# FanBot.net
KiCad netlist of a schematic drawn in Altium Designer
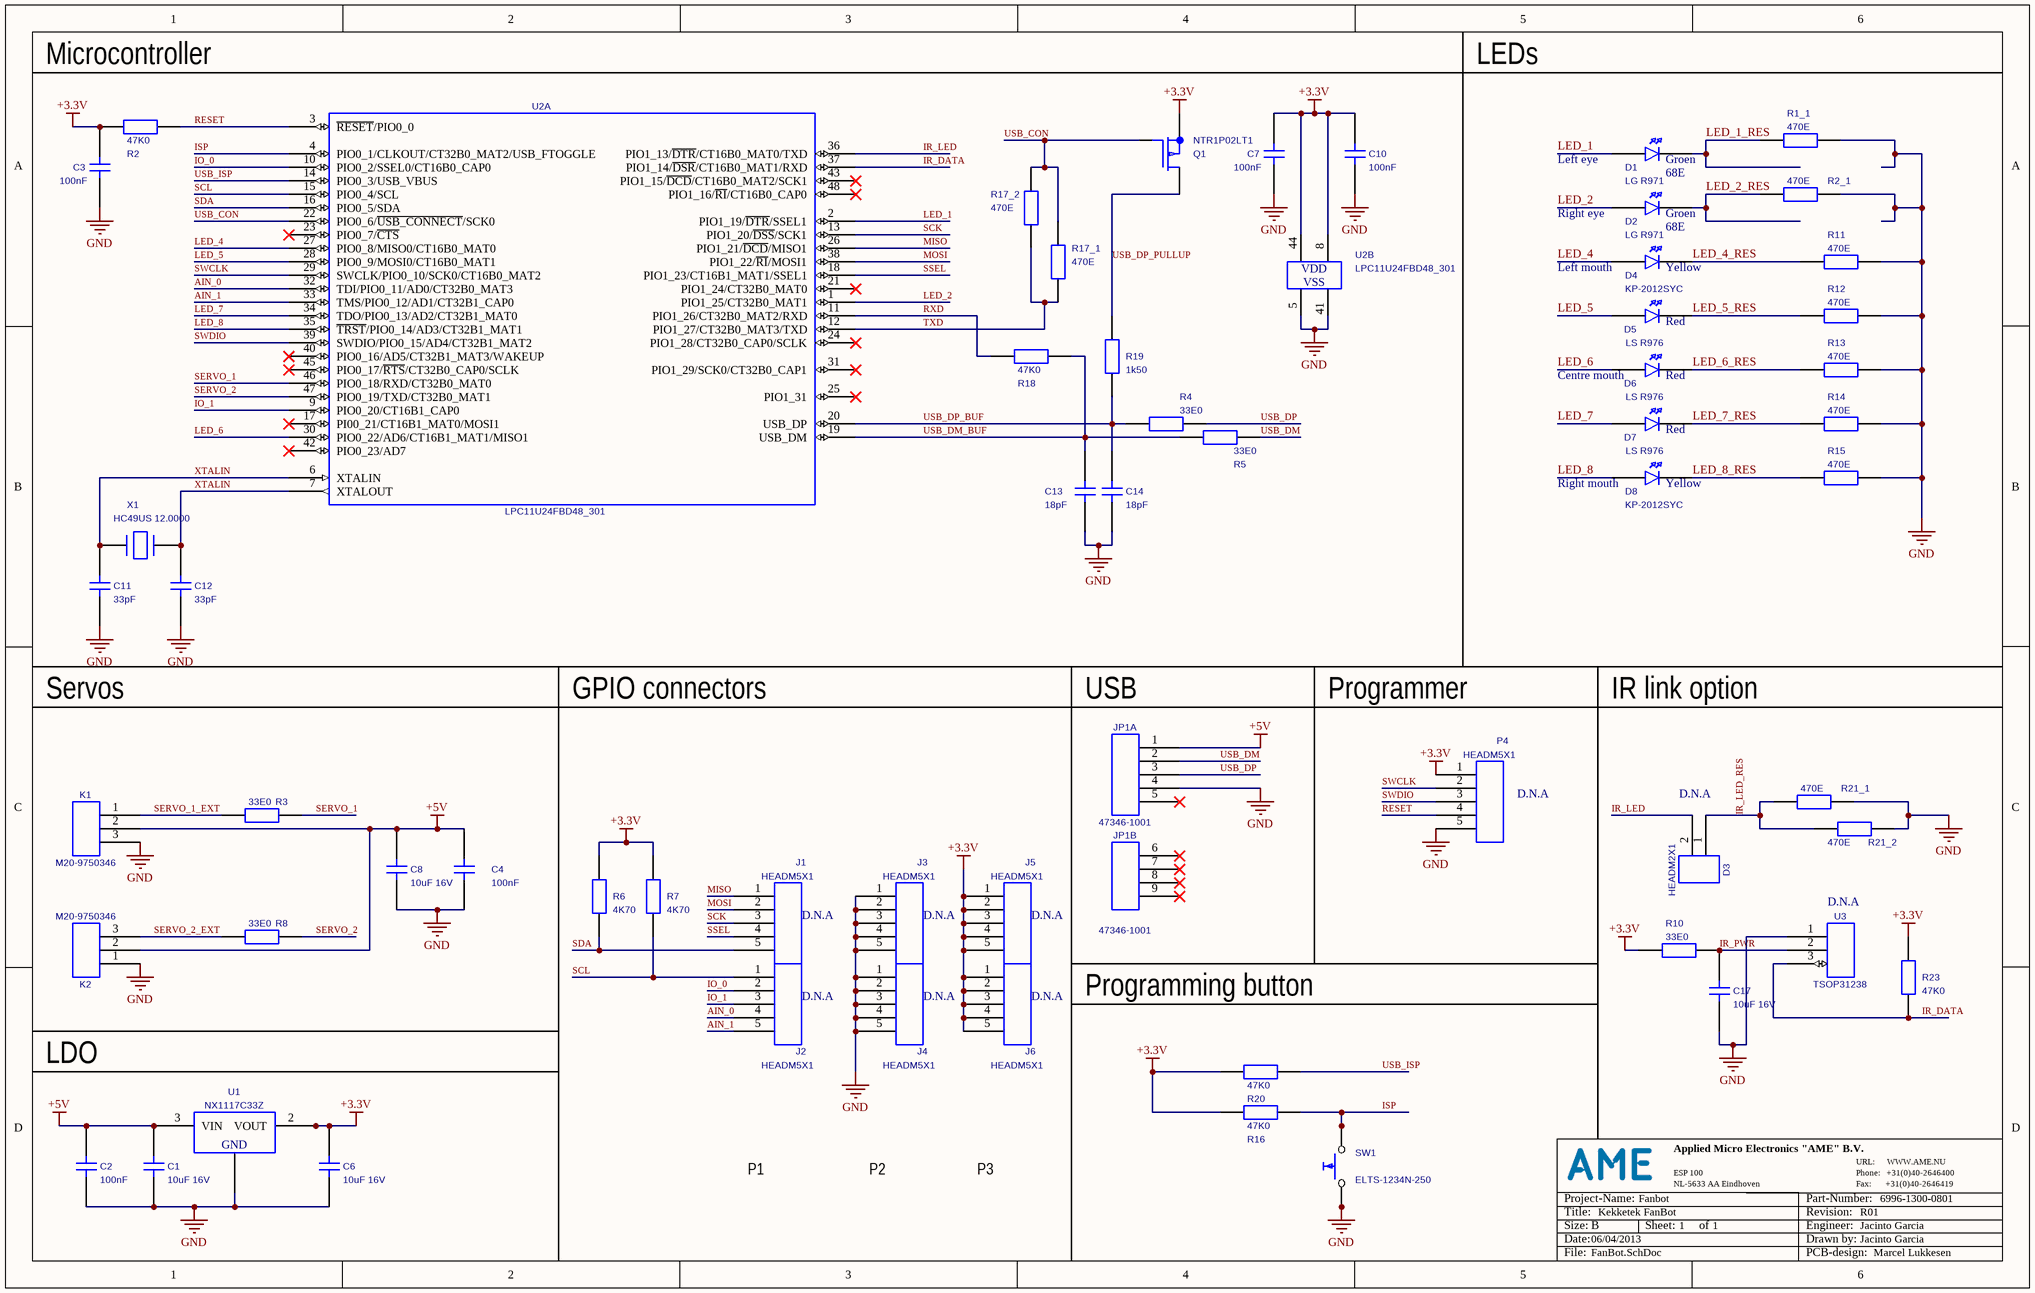
[diagram p0: FanBot.SchDoc]

(export (version "E")
  (design (tool "Eeschema 10.0.6"))
  (components
    (comp (ref "C1")
      (value "10U 0805 X5R16V")
      (footprint "C0805")
      (fields
        (field (name "PART NUMBER") "120400051105")
        (field (name "MANUFACTURER") "AVX")
        (field (name "PVALUE") "10uF 16V")
      )
      (libsource (lib "CC0805") (part "10U 0805 X5R16V"))
    )
    (comp (ref "C2")
      (value "100N 0805 X7R50V")
      (footprint "C0805")
      (fields
        (field (name "PVALUE") "100nF")
        (field (name "PART NUMBER") "120400011003")
        (field (name "MANUFACTURER") "Kemet")
      )
      (libsource (lib "CC0805") (part "100N 0805 X7R50V"))
    )
    (comp (ref "C3")
      (value "100N 0805 X7R50V")
      (footprint "C0805")
      (fields
        (field (name "PVALUE") "100nF")
        (field (name "PART NUMBER") "120400011003")
        (field (name "MANUFACTURER") "Kemet")
      )
      (libsource (lib "CC0805") (part "100N 0805 X7R50V"))
    )
    (comp (ref "C4")
      (value "100N 0805 X7R50V")
      (footprint "C0805")
      (fields
        (field (name "PVALUE") "100nF")
        (field (name "PART NUMBER") "120400011003")
        (field (name "MANUFACTURER") "Kemet")
      )
      (libsource (lib "CC0805") (part "100N 0805 X7R50V"))
    )
    (comp (ref "C6")
      (value "10U 0805 X5R16V")
      (footprint "C0805")
      (fields
        (field (name "PART NUMBER") "120400051105")
        (field (name "MANUFACTURER") "AVX")
        (field (name "PVALUE") "10uF 16V")
      )
      (libsource (lib "CC0805") (part "10U 0805 X5R16V"))
    )
    (comp (ref "C7")
      (value "100N 0805 X7R50V")
      (footprint "C0805")
      (fields
        (field (name "PVALUE") "100nF")
        (field (name "PART NUMBER") "120400011003")
        (field (name "MANUFACTURER") "Kemet")
      )
      (libsource (lib "CC0805") (part "100N 0805 X7R50V"))
    )
    (comp (ref "C8")
      (value "10U 0805 X5R16V")
      (footprint "C0805")
      (fields
        (field (name "PART NUMBER") "120400051105")
        (field (name "MANUFACTURER") "AVX")
        (field (name "PVALUE") "10uF 16V")
      )
      (libsource (lib "CC0805") (part "10U 0805 X5R16V"))
    )
    (comp (ref "C10")
      (value "100N 0805 X7R50V")
      (footprint "C0805")
      (fields
        (field (name "PVALUE") "100nF")
        (field (name "PART NUMBER") "120400011003")
        (field (name "MANUFACTURER") "Kemet")
      )
      (libsource (lib "CC0805") (part "100N 0805 X7R50V"))
    )
    (comp (ref "C11")
      (value "33P 0805 X7R50V")
      (footprint "C0805")
      (fields
        (field (name "PVALUE") "33pF")
        (field (name "PART NUMBER") "120400013309")
        (field (name "MANUFACTURER") "Kemet")
      )
      (libsource (lib "CC0805") (part "33P 0805 X7R50V"))
    )
    (comp (ref "C12")
      (value "33P 0805 X7R50V")
      (footprint "C0805")
      (fields
        (field (name "PVALUE") "33pF")
        (field (name "PART NUMBER") "120400013309")
        (field (name "MANUFACTURER") "Kemet")
      )
      (libsource (lib "CC0805") (part "33P 0805 X7R50V"))
    )
    (comp (ref "C13")
      (value "18P 0805 X7R50V")
      (footprint "C0805")
      (fields
        (field (name "PVALUE") "18pF")
        (field (name "PART NUMBER") "120400011809")
        (field (name "MANUFACTURER") "Kemet")
      )
      (libsource (lib "CC0805") (part "18P 0805 X7R50V"))
    )
    (comp (ref "C14")
      (value "18P 0805 X7R50V")
      (footprint "C0805")
      (fields
        (field (name "PVALUE") "18pF")
        (field (name "PART NUMBER") "120400011809")
        (field (name "MANUFACTURER") "Kemet")
      )
      (libsource (lib "CC0805") (part "18P 0805 X7R50V"))
    )
    (comp (ref "C17")
      (value "10U 0805 X5R16V")
      (footprint "C0805")
      (fields
        (field (name "PART NUMBER") "120400051105")
        (field (name "MANUFACTURER") "AVX")
        (field (name "PVALUE") "10uF 16V")
      )
      (libsource (lib "CC0805") (part "10U 0805 X5R16V"))
    )
    (comp (ref "D1")
      (value "LG R971")
      (footprint "0805 LED OSR")
      (fields (field (name "PART NUMBER") "206000010001") (field (name "MANUFACTURER") "Osram"))
      (libsource (lib "DIS_AM") (part "LG R971"))
    )
    (comp (ref "D2")
      (value "LG R971")
      (footprint "0805 LED OSR")
      (fields (field (name "PART NUMBER") "206000010001") (field (name "MANUFACTURER") "Osram"))
      (libsource (lib "DIS_AM") (part "LG R971"))
    )
    (comp (ref "D3")
      (value "HEADM2X1")
      (footprint "HEADM2X1")
      (fields (field (name "PART NUMBER") "505000030003") (field (name "MANUFACTURER") "Harwin"))
      (libsource (lib "CONN_AM") (part "HEADM2X1"))
    )
    (comp (ref "D4")
      (value "KP-2012SYC")
      (footprint "0805 LED")
      (fields (field (name "PART NUMBER") "206000010035") (field (name "MANUFACTURER") "Kingbright"))
      (libsource (lib "DIS_AM") (part "KP-2012SYC"))
    )
    (comp (ref "D5")
      (value "LS R976")
      (footprint "0805 LED OSR")
      (fields (field (name "PART NUMBER") "206000010024") (field (name "MANUFACTURER") "Osram"))
      (libsource (lib "DIS_AM") (part "LS R976"))
    )
    (comp (ref "D6")
      (value "LS R976")
      (footprint "0805 LED OSR")
      (fields (field (name "PART NUMBER") "206000010024") (field (name "MANUFACTURER") "Osram"))
      (libsource (lib "DIS_AM") (part "LS R976"))
    )
    (comp (ref "D7")
      (value "LS R976")
      (footprint "0805 LED OSR")
      (fields (field (name "PART NUMBER") "206000010024") (field (name "MANUFACTURER") "Osram"))
      (libsource (lib "DIS_AM") (part "LS R976"))
    )
    (comp (ref "D8")
      (value "KP-2012SYC")
      (footprint "0805 LED")
      (fields (field (name "PART NUMBER") "206000010035") (field (name "MANUFACTURER") "Kingbright"))
      (libsource (lib "DIS_AM") (part "KP-2012SYC"))
    )
    (comp (ref "J1")
      (value "HEADM5X1")
      (footprint "M20-9770522")
      (fields (field (name "PART NUMBER") "505000080023") (field (name "MANUFACTURER") "Harwin"))
      (libsource (lib "CONN_AM") (part "HEADM5X1"))
    )
    (comp (ref "J2")
      (value "HEADM5X1")
      (footprint "M20-9770522")
      (fields (field (name "PART NUMBER") "505000080023") (field (name "MANUFACTURER") "Harwin"))
      (libsource (lib "CONN_AM") (part "HEADM5X1"))
    )
    (comp (ref "J3")
      (value "HEADM5X1")
      (footprint "M20-9770522")
      (fields (field (name "PART NUMBER") "505000080023") (field (name "MANUFACTURER") "Harwin"))
      (libsource (lib "CONN_AM") (part "HEADM5X1"))
    )
    (comp (ref "J4")
      (value "HEADM5X1")
      (footprint "M20-9770522")
      (fields (field (name "PART NUMBER") "505000080023") (field (name "MANUFACTURER") "Harwin"))
      (libsource (lib "CONN_AM") (part "HEADM5X1"))
    )
    (comp (ref "J5")
      (value "HEADM5X1")
      (footprint "M20-9770522")
      (fields (field (name "PART NUMBER") "505000080023") (field (name "MANUFACTURER") "Harwin"))
      (libsource (lib "CONN_AM") (part "HEADM5X1"))
    )
    (comp (ref "J6")
      (value "HEADM5X1")
      (footprint "M20-9770522")
      (fields (field (name "PART NUMBER") "505000080023") (field (name "MANUFACTURER") "Harwin"))
      (libsource (lib "CONN_AM") (part "HEADM5X1"))
    )
    (comp (ref "JP1")
      (value "47346-1001")
      (footprint "47346-0001")
      (fields (field (name "PART NUMBER") "509000220067") (field (name "MANUFACTURER") "Molex"))
      (libsource (lib "CONN_AM") (part "47346-1001"))
    )
    (comp (ref "K1")
      (value "M20-9750346")
      (footprint "M20-9750346")
      (fields (field (name "PART NUMBER") "505000080120") (field (name "MANUFACTURER") "Harwin"))
      (libsource (lib "CONN_AM") (part "M20-9750346"))
    )
    (comp (ref "K2")
      (value "M20-9750346")
      (footprint "M20-9750346")
      (fields (field (name "PART NUMBER") "505000080120") (field (name "MANUFACTURER") "Harwin"))
      (libsource (lib "CONN_AM") (part "M20-9750346"))
    )
    (comp (ref "P4")
      (value "HEADM5X1")
      (footprint "M20-9770522")
      (fields (field (name "PART NUMBER") "505000080023") (field (name "MANUFACTURER") "Harwin"))
      (libsource (lib "CONN_AM") (part "HEADM5X1"))
    )
    (comp (ref "Q1")
      (value "NTR1P02LT1")
      (footprint "SOT-23")
      (fields (field (name "PART NUMBER") "222000010018") (field (name "MANUFACTURER") "ON Semiconductor"))
      (libsource (lib "DIS_AM") (part "NTR1P02LT1"))
    )
    (comp (ref "R1_1")
      (value "470E 0805 1%")
      (footprint "R0805")
      (fields
        (field (name "PVALUE") "470E")
        (field (name "PART NUMBER") "110200014700")
        (field (name "MANUFACTURER") "ASJ")
      )
      (libsource (lib "RM08051") (part "470E 0805 1%"))
    )
    (comp (ref "R2")
      (value "47K0 0805 1%")
      (footprint "R0805")
      (fields
        (field (name "PVALUE") "47K0")
        (field (name "PART NUMBER") "110200014702")
        (field (name "MANUFACTURER") "ASJ")
      )
      (libsource (lib "RM08051") (part "47K0 0805 1%"))
    )
    (comp (ref "R2_1")
      (value "470E 0805 1%")
      (footprint "R0805")
      (fields
        (field (name "PVALUE") "470E")
        (field (name "PART NUMBER") "110200014700")
        (field (name "MANUFACTURER") "ASJ")
      )
      (libsource (lib "RM08051") (part "470E 0805 1%"))
    )
    (comp (ref "R3")
      (value "33E0 0805 1%")
      (footprint "R0805")
      (fields
        (field (name "PART NUMBER") "110200013309")
        (field (name "MANUFACTURER") "Yageo")
        (field (name "PVALUE") "33E0")
      )
      (libsource (lib "RM08051") (part "33E0 0805 1%"))
    )
    (comp (ref "R4")
      (value "33E0 0805 1%")
      (footprint "R0805")
      (fields
        (field (name "PART NUMBER") "110200013309")
        (field (name "MANUFACTURER") "Yageo")
        (field (name "PVALUE") "33E0")
      )
      (libsource (lib "RM08051") (part "33E0 0805 1%"))
    )
    (comp (ref "R5")
      (value "33E0 0805 1%")
      (footprint "R0805")
      (fields
        (field (name "PART NUMBER") "110200013309")
        (field (name "MANUFACTURER") "Yageo")
        (field (name "PVALUE") "33E0")
      )
      (libsource (lib "RM08051") (part "33E0 0805 1%"))
    )
    (comp (ref "R6")
      (value "4K70 0805 1%")
      (footprint "R0805")
      (fields
        (field (name "PVALUE") "4K70")
        (field (name "PART NUMBER") "110200014701")
        (field (name "MANUFACTURER") "ASJ")
      )
      (libsource (lib "RM08051") (part "4K70 0805 1%"))
    )
    (comp (ref "R7")
      (value "4K70 0805 1%")
      (footprint "R0805")
      (fields
        (field (name "PVALUE") "4K70")
        (field (name "PART NUMBER") "110200014701")
        (field (name "MANUFACTURER") "ASJ")
      )
      (libsource (lib "RM08051") (part "4K70 0805 1%"))
    )
    (comp (ref "R8")
      (value "33E0 0805 1%")
      (footprint "R0805")
      (fields
        (field (name "PART NUMBER") "110200013309")
        (field (name "MANUFACTURER") "Yageo")
        (field (name "PVALUE") "33E0")
      )
      (libsource (lib "RM08051") (part "33E0 0805 1%"))
    )
    (comp (ref "R10")
      (value "33E0 0805 1%")
      (footprint "R0805")
      (fields
        (field (name "PVALUE") "33E0")
        (field (name "PART NUMBER") "110200013309")
        (field (name "MANUFACTURER") "Yageo")
      )
      (libsource (lib "RM08051") (part "33E0 0805 1%"))
    )
    (comp (ref "R11")
      (value "470E 0805 1%")
      (footprint "R0805")
      (fields
        (field (name "PVALUE") "470E")
        (field (name "PART NUMBER") "110200014700")
        (field (name "MANUFACTURER") "ASJ")
      )
      (libsource (lib "RM08051") (part "470E 0805 1%"))
    )
    (comp (ref "R12")
      (value "470E 0805 1%")
      (footprint "R0805")
      (fields
        (field (name "PVALUE") "470E")
        (field (name "PART NUMBER") "110200014700")
        (field (name "MANUFACTURER") "ASJ")
      )
      (libsource (lib "RM08051") (part "470E 0805 1%"))
    )
    (comp (ref "R13")
      (value "470E 0805 1%")
      (footprint "R0805")
      (fields
        (field (name "PVALUE") "470E")
        (field (name "PART NUMBER") "110200014700")
        (field (name "MANUFACTURER") "ASJ")
      )
      (libsource (lib "RM08051") (part "470E 0805 1%"))
    )
    (comp (ref "R14")
      (value "470E 0805 1%")
      (footprint "R0805")
      (fields
        (field (name "PVALUE") "470E")
        (field (name "PART NUMBER") "110200014700")
        (field (name "MANUFACTURER") "ASJ")
      )
      (libsource (lib "RM08051") (part "470E 0805 1%"))
    )
    (comp (ref "R15")
      (value "470E 0805 1%")
      (footprint "R0805")
      (fields
        (field (name "PVALUE") "470E")
        (field (name "PART NUMBER") "110200014700")
        (field (name "MANUFACTURER") "ASJ")
      )
      (libsource (lib "RM08051") (part "470E 0805 1%"))
    )
    (comp (ref "R16")
      (value "47K0 0805 1%")
      (footprint "R0805")
      (fields
        (field (name "PVALUE") "47K0")
        (field (name "PART NUMBER") "110200014702")
        (field (name "MANUFACTURER") "ASJ")
      )
      (libsource (lib "RM08051") (part "47K0 0805 1%"))
    )
    (comp (ref "R17_1")
      (value "470E 0805 1%")
      (footprint "R0805")
      (fields
        (field (name "PVALUE") "470E")
        (field (name "PART NUMBER") "110200014700")
        (field (name "MANUFACTURER") "ASJ")
      )
      (libsource (lib "RM08051") (part "470E 0805 1%"))
    )
    (comp (ref "R17_2")
      (value "470E 0805 1%")
      (footprint "R0805")
      (fields
        (field (name "PVALUE") "470E")
        (field (name "PART NUMBER") "110200014700")
        (field (name "MANUFACTURER") "ASJ")
      )
      (libsource (lib "RM08051") (part "470E 0805 1%"))
    )
    (comp (ref "R18")
      (value "47K0 0805 1%")
      (footprint "R0805")
      (fields
        (field (name "PVALUE") "47K0")
        (field (name "PART NUMBER") "110200014702")
        (field (name "MANUFACTURER") "ASJ")
      )
      (libsource (lib "RM08051") (part "47K0 0805 1%"))
    )
    (comp (ref "R19")
      (value "1K50 0805 1%")
      (footprint "R0805")
      (fields
        (field (name "PVALUE") "1k50")
        (field (name "PART NUMBER") "110200011501")
        (field (name "MANUFACTURER") "ASJ")
      )
      (libsource (lib "RM08051") (part "1K50 0805 1%"))
    )
    (comp (ref "R20")
      (value "47K0 0805 1%")
      (footprint "R0805")
      (fields
        (field (name "PVALUE") "47K0")
        (field (name "PART NUMBER") "110200014702")
        (field (name "MANUFACTURER") "ASJ")
      )
      (libsource (lib "RM08051") (part "47K0 0805 1%"))
    )
    (comp (ref "R21_1")
      (value "470E 0805 1%")
      (footprint "R0805")
      (fields
        (field (name "PVALUE") "470E")
        (field (name "PART NUMBER") "110200014700")
        (field (name "MANUFACTURER") "ASJ")
      )
      (libsource (lib "RM08051") (part "470E 0805 1%"))
    )
    (comp (ref "R21_2")
      (value "470E 0805 1%")
      (footprint "R0805")
      (fields
        (field (name "PVALUE") "470E")
        (field (name "PART NUMBER") "110200014700")
        (field (name "MANUFACTURER") "ASJ")
      )
      (libsource (lib "RM08051") (part "470E 0805 1%"))
    )
    (comp (ref "R23")
      (value "47K0 0805 1%")
      (footprint "R0805")
      (fields
        (field (name "PVALUE") "47K0")
        (field (name "PART NUMBER") "110200014702")
        (field (name "MANUFACTURER") "ASJ")
      )
      (libsource (lib "RM08051") (part "47K0 0805 1%"))
    )
    (comp (ref "SW1")
      (value "ELTS-1234N-250")
      (footprint "ELTS-1234N")
      (fields (field (name "PART NUMBER") "513000010022") (field (name "MANUFACTURER") "Eledis"))
      (libsource (lib "ELEC_AM") (part "ELTS-1234N-250"))
    )
    (comp (ref "U1")
      (value "NX1117C33Z")
      (footprint "SOT-223")
      (fields (field (name "PART NUMBER") "330000010048") (field (name "MANUFACTURER") "NXP Semiconductor"))
      (libsource (lib "REGULATORS") (part "NX1117C33Z"))
    )
    (comp (ref "U2")
      (value "LPC11U24FBD48_301")
      (footprint "LQFP48")
      (fields (field (name "PART NUMBER") "411000010007") (field (name "MANUFACTURER") "NXP Semiconductor"))
      (libsource (lib "MICRO") (part "LPC11U24FBD48_301"))
    )
    (comp (ref "U3")
      (value "TSOP31238")
      (footprint "TSOP312")
      (fields (field (name "PART NUMBER") "324000010007") (field (name "MANUFACTURER") "Vishay"))
      (libsource (lib "DIS_AM") (part "TSOP31238"))
    )
    (comp (ref "X1")
      (value "HC49US 12.0000")
      (footprint "HC49/4HSMX")
      (fields (field (name "PART NUMBER") "140000010015") (field (name "MANUFACTURER") "Hong Kong Crystals"))
      (libsource (lib "XTAL") (part "HC49US 12.0000"))
    )
  )
  (nets
    (net (code "1") (name "+3.3V") (class "Default")
      (node (ref "C10") (pin "1") (pinfunction "1_1") (pintype "passive"))
      (node (ref "C3") (pin "1") (pinfunction "1_1") (pintype "passive"))
      (node (ref "C6") (pin "1") (pinfunction "1_1") (pintype "passive"))
      (node (ref "C7") (pin "1") (pinfunction "1_1") (pintype "passive"))
      (node (ref "J5") (pin "1") (pinfunction "A1_1") (pintype "passive"))
      (node (ref "J5") (pin "2") (pinfunction "A2_2") (pintype "passive"))
      (node (ref "J5") (pin "3") (pinfunction "A3_3") (pintype "passive"))
      (node (ref "J5") (pin "4") (pinfunction "A4_4") (pintype "passive"))
      (node (ref "J5") (pin "5") (pinfunction "A5_5") (pintype "passive"))
      (node (ref "J6") (pin "1") (pinfunction "A1_1") (pintype "passive"))
      (node (ref "J6") (pin "2") (pinfunction "A2_2") (pintype "passive"))
      (node (ref "J6") (pin "3") (pinfunction "A3_3") (pintype "passive"))
      (node (ref "J6") (pin "4") (pinfunction "A4_4") (pintype "passive"))
      (node (ref "J6") (pin "5") (pinfunction "A5_5") (pintype "passive"))
      (node (ref "P4") (pin "1") (pinfunction "A1_1") (pintype "passive"))
      (node (ref "Q1") (pin "2") (pinfunction "S_2") (pintype "passive"))
      (node (ref "R10") (pin "1") (pinfunction "1_1") (pintype "passive"))
      (node (ref "R16") (pin "2") (pinfunction "2_2") (pintype "passive"))
      (node (ref "R2") (pin "2") (pinfunction "2_2") (pintype "passive"))
      (node (ref "R20") (pin "2") (pinfunction "2_2") (pintype "passive"))
      (node (ref "R23") (pin "1") (pinfunction "1_1") (pintype "passive"))
      (node (ref "R6") (pin "1") (pinfunction "1_1") (pintype "passive"))
      (node (ref "R7") (pin "1") (pinfunction "1_1") (pintype "passive"))
      (node (ref "U1") (pin "2") (pinfunction "VOUT_2") (pintype "power_in"))
      (node (ref "U1") (pin "4") (pinfunction "VOUT_4") (pintype "power_in"))
      (node (ref "U2") (pin "44") (pinfunction "VDD_44") (pintype "power_in"))
      (node (ref "U2") (pin "8") (pinfunction "VDD_8") (pintype "power_in"))
    )
    (net (code "2") (name "+5V") (class "Default")
      (node (ref "C1") (pin "1") (pinfunction "1_1") (pintype "passive"))
      (node (ref "C2") (pin "1") (pinfunction "1_1") (pintype "passive"))
      (node (ref "C4") (pin "1") (pinfunction "1_1") (pintype "passive"))
      (node (ref "C8") (pin "1") (pinfunction "1_1") (pintype "passive"))
      (node (ref "JP1") (pin "1") (pinfunction "VBUS_1") (pintype "passive"))
      (node (ref "K1") (pin "2") (pinfunction "2_2") (pintype "passive"))
      (node (ref "K2") (pin "2") (pinfunction "2_2") (pintype "passive"))
      (node (ref "U1") (pin "3") (pinfunction "VIN_3") (pintype "power_in"))
    )
    (net (code "3") (name "/AIN_0") (class "Default")
      (node (ref "J2") (pin "4") (pinfunction "A4_4") (pintype "passive"))
      (node (ref "U2") (pin "32") (pinfunction "TDI/PIO0_11/AD0/CT32B0_MAT3_32") (pintype "bidirectional"))
    )
    (net (code "4") (name "/AIN_1") (class "Default")
      (node (ref "J2") (pin "5") (pinfunction "A5_5") (pintype "passive"))
      (node (ref "U2") (pin "33") (pinfunction "TMS/PIO0_12/AD1/CT32B1_CAP0_33") (pintype "bidirectional"))
    )
    (net (code "5") (name "/IO_0") (class "Default")
      (node (ref "J2") (pin "2") (pinfunction "A2_2") (pintype "passive"))
      (node (ref "U2") (pin "10") (pinfunction "PIO0_2/SSEL0/CT16B0_CAP0_10") (pintype "bidirectional"))
    )
    (net (code "6") (name "/IO_1") (class "Default")
      (node (ref "J2") (pin "3") (pinfunction "A3_3") (pintype "passive"))
      (node (ref "U2") (pin "9") (pinfunction "PIO0_20/CT16B1_CAP0_9") (pintype "bidirectional"))
    )
    (net (code "7") (name "/IR_DATA") (class "Default")
      (node (ref "R23") (pin "2") (pinfunction "2_2") (pintype "passive"))
      (node (ref "U2") (pin "37") (pinfunction "PIO1_14/~{DSR}/CT16B0_MAT1/RXD_37") (pintype "bidirectional"))
      (node (ref "U3") (pin "3") (pinfunction "OUT_3") (pintype "bidirectional"))
    )
    (net (code "8") (name "/IR_LED") (class "Default")
      (node (ref "D3") (pin "2") (pintype "passive"))
      (node (ref "U2") (pin "36") (pinfunction "PIO1_13/~{DTR}/CT16B0_MAT0/TXD_36") (pintype "bidirectional"))
    )
    (net (code "9") (name "/IR_LED_RES") (class "Default")
      (node (ref "D3") (pin "1") (pintype "passive"))
      (node (ref "R21_1") (pin "1") (pinfunction "1_1") (pintype "passive"))
      (node (ref "R21_2") (pin "1") (pinfunction "1_1") (pintype "passive"))
    )
    (net (code "10") (name "/IR_PWR") (class "Default")
      (node (ref "C17") (pin "1") (pinfunction "1_1") (pintype "passive"))
      (node (ref "R10") (pin "2") (pinfunction "2_2") (pintype "passive"))
      (node (ref "U3") (pin "2") (pinfunction "VS_2") (pintype "power_in"))
    )
    (net (code "11") (name "/ISP") (class "Default")
      (node (ref "R16") (pin "1") (pinfunction "1_1") (pintype "passive"))
      (node (ref "SW1") (pin "1") (pintype "passive"))
      (node (ref "SW1") (pin "3") (pintype "passive"))
      (node (ref "U2") (pin "4") (pinfunction "PIO0_1/CLKOUT/CT32B0_MAT2/USB_FTOGGLE_4") (pintype "bidirectional"))
    )
    (net (code "12") (name "/LED_1") (class "Default")
      (node (ref "D1") (pin "2") (pinfunction "A_2") (pintype "passive"))
      (node (ref "U2") (pin "2") (pinfunction "PIO1_19/~{DTR}/SSEL1_2") (pintype "bidirectional"))
    )
    (net (code "13") (name "/LED_1_RES") (class "Default")
      (node (ref "D1") (pin "1") (pinfunction "K_1") (pintype "passive"))
      (node (ref "R1_1") (pin "1") (pinfunction "1_1") (pintype "passive"))
    )
    (net (code "14") (name "/LED_2") (class "Default")
      (node (ref "D2") (pin "2") (pinfunction "A_2") (pintype "passive"))
      (node (ref "U2") (pin "1") (pinfunction "PIO1_25/CT32B0_MAT1_1") (pintype "bidirectional"))
    )
    (net (code "15") (name "/LED_2_RES") (class "Default")
      (node (ref "D2") (pin "1") (pinfunction "K_1") (pintype "passive"))
      (node (ref "R2_1") (pin "1") (pinfunction "1_1") (pintype "passive"))
    )
    (net (code "16") (name "/LED_4") (class "Default")
      (node (ref "D4") (pin "2") (pinfunction "A_2") (pintype "passive"))
      (node (ref "U2") (pin "27") (pinfunction "PIO0_8/MISO0/CT16B0_MAT0_27") (pintype "bidirectional"))
    )
    (net (code "17") (name "/LED_4_RES") (class "Default")
      (node (ref "D4") (pin "1") (pinfunction "K_1") (pintype "passive"))
      (node (ref "R11") (pin "1") (pinfunction "1_1") (pintype "passive"))
    )
    (net (code "18") (name "/LED_5") (class "Default")
      (node (ref "D5") (pin "2") (pinfunction "A_2") (pintype "passive"))
      (node (ref "U2") (pin "28") (pinfunction "PIO0_9/MOSI0/CT16B0_MAT1_28") (pintype "bidirectional"))
    )
    (net (code "19") (name "/LED_5_RES") (class "Default")
      (node (ref "D5") (pin "1") (pinfunction "K_1") (pintype "passive"))
      (node (ref "R12") (pin "1") (pinfunction "1_1") (pintype "passive"))
    )
    (net (code "20") (name "/LED_6") (class "Default")
      (node (ref "D6") (pin "2") (pinfunction "A_2") (pintype "passive"))
      (node (ref "U2") (pin "30") (pinfunction "PIO0_22/AD6/CT16B1_MAT1/MISO1_30") (pintype "bidirectional"))
    )
    (net (code "21") (name "/LED_6_RES") (class "Default")
      (node (ref "D6") (pin "1") (pinfunction "K_1") (pintype "passive"))
      (node (ref "R13") (pin "1") (pinfunction "1_1") (pintype "passive"))
    )
    (net (code "22") (name "/LED_7") (class "Default")
      (node (ref "D7") (pin "2") (pinfunction "A_2") (pintype "passive"))
      (node (ref "U2") (pin "34") (pinfunction "TDO/PIO0_13/AD2/CT32B1_MAT0_34") (pintype "bidirectional"))
    )
    (net (code "23") (name "/LED_7_RES") (class "Default")
      (node (ref "D7") (pin "1") (pinfunction "K_1") (pintype "passive"))
      (node (ref "R14") (pin "1") (pinfunction "1_1") (pintype "passive"))
    )
    (net (code "24") (name "/LED_8") (class "Default")
      (node (ref "D8") (pin "2") (pinfunction "A_2") (pintype "passive"))
      (node (ref "U2") (pin "35") (pinfunction "~{TRST}/PIO0_14/AD3/CT32B1_MAT1_35") (pintype "bidirectional"))
    )
    (net (code "25") (name "/LED_8_RES") (class "Default")
      (node (ref "D8") (pin "1") (pinfunction "K_1") (pintype "passive"))
      (node (ref "R15") (pin "1") (pinfunction "1_1") (pintype "passive"))
    )
    (net (code "26") (name "/MISO") (class "Default")
      (node (ref "J1") (pin "1") (pinfunction "A1_1") (pintype "passive"))
      (node (ref "U2") (pin "26") (pinfunction "PIO1_21/~{DCD}/MISO1_26") (pintype "bidirectional"))
    )
    (net (code "27") (name "/MOSI") (class "Default")
      (node (ref "J1") (pin "2") (pinfunction "A2_2") (pintype "passive"))
      (node (ref "U2") (pin "38") (pinfunction "PIO1_22/~{RI}/MOSI1_38") (pintype "bidirectional"))
    )
    (net (code "28") (name "/RESET") (class "Default")
      (node (ref "P4") (pin "4") (pinfunction "A4_4") (pintype "passive"))
      (node (ref "R2") (pin "1") (pinfunction "1_1") (pintype "passive"))
      (node (ref "U2") (pin "3") (pinfunction "~{RESET}/PIO0_0_3") (pintype "bidirectional"))
    )
    (net (code "29") (name "/RXD") (class "Default")
      (node (ref "R18") (pin "2") (pinfunction "2_2") (pintype "passive"))
      (node (ref "U2") (pin "11") (pinfunction "PIO1_26/CT32B0_MAT2/RXD_11") (pintype "bidirectional"))
    )
    (net (code "30") (name "/SCK") (class "Default")
      (node (ref "J1") (pin "3") (pinfunction "A3_3") (pintype "passive"))
      (node (ref "U2") (pin "13") (pinfunction "PIO1_20/~{DSS}/SCK1_13") (pintype "bidirectional"))
    )
    (net (code "31") (name "/SCL") (class "Default")
      (node (ref "J2") (pin "1") (pinfunction "A1_1") (pintype "passive"))
      (node (ref "R7") (pin "2") (pinfunction "2_2") (pintype "passive"))
      (node (ref "U2") (pin "15") (pinfunction "PIO0_4/SCL_15") (pintype "bidirectional"))
    )
    (net (code "32") (name "/SDA") (class "Default")
      (node (ref "J1") (pin "5") (pinfunction "A5_5") (pintype "passive"))
      (node (ref "R6") (pin "2") (pinfunction "2_2") (pintype "passive"))
      (node (ref "U2") (pin "16") (pinfunction "PIO0_5/SDA_16") (pintype "bidirectional"))
    )
    (net (code "33") (name "/SERVO_1") (class "Default")
      (node (ref "R3") (pin "2") (pinfunction "2_2") (pintype "passive"))
      (node (ref "U2") (pin "46") (pinfunction "PIO0_18/RXD/CT32B0_MAT0_46") (pintype "bidirectional"))
    )
    (net (code "34") (name "/SERVO_1_EXT") (class "Default")
      (node (ref "K1") (pin "1") (pinfunction "1_1") (pintype "passive"))
      (node (ref "R3") (pin "1") (pinfunction "1_1") (pintype "passive"))
    )
    (net (code "35") (name "/SERVO_2") (class "Default")
      (node (ref "R8") (pin "2") (pinfunction "2_2") (pintype "passive"))
      (node (ref "U2") (pin "47") (pinfunction "PIO0_19/TXD/CT32B0_MAT1_47") (pintype "bidirectional"))
    )
    (net (code "36") (name "/SERVO_2_EXT") (class "Default")
      (node (ref "K2") (pin "3") (pinfunction "3_3") (pintype "passive"))
      (node (ref "R8") (pin "1") (pinfunction "1_1") (pintype "passive"))
    )
    (net (code "37") (name "/SSEL") (class "Default")
      (node (ref "J1") (pin "4") (pinfunction "A4_4") (pintype "passive"))
      (node (ref "U2") (pin "18") (pinfunction "PIO1_23/CT16B1_MAT1/SSEL1_18") (pintype "bidirectional"))
    )
    (net (code "38") (name "/SWCLK") (class "Default")
      (node (ref "P4") (pin "2") (pinfunction "A2_2") (pintype "passive"))
      (node (ref "U2") (pin "29") (pinfunction "SWCLK/PIO0_10/SCK0/CT16B0_MAT2_29") (pintype "bidirectional"))
    )
    (net (code "39") (name "/SWDIO") (class "Default")
      (node (ref "P4") (pin "3") (pinfunction "A3_3") (pintype "passive"))
      (node (ref "U2") (pin "39") (pinfunction "SWDIO/PIO0_15/AD4/CT32B1_MAT2_39") (pintype "bidirectional"))
    )
    (net (code "40") (name "/TXD") (class "Default")
      (node (ref "R17_1") (pin "2") (pinfunction "2_2") (pintype "passive"))
      (node (ref "R17_2") (pin "2") (pinfunction "2_2") (pintype "passive"))
      (node (ref "U2") (pin "12") (pinfunction "PIO1_27/CT32B0_MAT3/TXD_12") (pintype "bidirectional"))
    )
    (net (code "41") (name "/USB_CON") (class "Default")
      (node (ref "Q1") (pin "1") (pinfunction "G_1") (pintype "passive"))
      (node (ref "R17_1") (pin "1") (pinfunction "1_1") (pintype "passive"))
      (node (ref "R17_2") (pin "1") (pinfunction "1_1") (pintype "passive"))
      (node (ref "U2") (pin "22") (pinfunction "PIO0_6/~{USB_CONNECT}/SCK0_22") (pintype "bidirectional"))
    )
    (net (code "42") (name "/USB_DM") (class "Default")
      (node (ref "JP1") (pin "2") (pinfunction "D-_2") (pintype "passive"))
      (node (ref "R5") (pin "2") (pinfunction "2_2") (pintype "passive"))
    )
    (net (code "43") (name "/USB_DM_BUF") (class "Default")
      (node (ref "C13") (pin "1") (pinfunction "1_1") (pintype "passive"))
      (node (ref "R18") (pin "1") (pinfunction "1_1") (pintype "passive"))
      (node (ref "R5") (pin "1") (pinfunction "1_1") (pintype "passive"))
      (node (ref "U2") (pin "19") (pinfunction "USB_DM_19") (pintype "bidirectional"))
    )
    (net (code "44") (name "/USB_DP") (class "Default")
      (node (ref "JP1") (pin "3") (pinfunction "D+_3") (pintype "passive"))
      (node (ref "R4") (pin "2") (pinfunction "2_2") (pintype "passive"))
    )
    (net (code "45") (name "/USB_DP_BUF") (class "Default")
      (node (ref "C14") (pin "1") (pinfunction "1_1") (pintype "passive"))
      (node (ref "R19") (pin "2") (pinfunction "2_2") (pintype "passive"))
      (node (ref "R4") (pin "1") (pinfunction "1_1") (pintype "passive"))
      (node (ref "U2") (pin "20") (pinfunction "USB_DP_20") (pintype "bidirectional"))
    )
    (net (code "46") (name "/USB_DP_PULLUP") (class "Default")
      (node (ref "Q1") (pin "3") (pinfunction "D_3") (pintype "passive"))
      (node (ref "R19") (pin "1") (pinfunction "1_1") (pintype "passive"))
    )
    (net (code "47") (name "/USB_ISP") (class "Default")
      (node (ref "R20") (pin "1") (pinfunction "1_1") (pintype "passive"))
      (node (ref "U2") (pin "14") (pinfunction "PIO0_3/USB_VBUS_14") (pintype "bidirectional"))
    )
    (net (code "48") (name "/XTALIN") (class "Default")
      (node (ref "C11") (pin "1") (pinfunction "1_1") (pintype "passive"))
      (node (ref "C12") (pin "1") (pinfunction "1_1") (pintype "passive"))
      (node (ref "U2") (pin "6") (pinfunction "XTALIN_6") (pintype "input"))
      (node (ref "U2") (pin "7") (pinfunction "XTALOUT_7") (pintype "output"))
      (node (ref "X1") (pin "1") (pintype "passive"))
      (node (ref "X1") (pin "2") (pintype "passive"))
    )
    (net (code "49") (name "GND") (class "Default")
      (node (ref "C1") (pin "2") (pinfunction "2_2") (pintype "passive"))
      (node (ref "C10") (pin "2") (pinfunction "2_2") (pintype "passive"))
      (node (ref "C11") (pin "2") (pinfunction "2_2") (pintype "passive"))
      (node (ref "C12") (pin "2") (pinfunction "2_2") (pintype "passive"))
      (node (ref "C13") (pin "2") (pinfunction "2_2") (pintype "passive"))
      (node (ref "C14") (pin "2") (pinfunction "2_2") (pintype "passive"))
      (node (ref "C17") (pin "2") (pinfunction "2_2") (pintype "passive"))
      (node (ref "C2") (pin "2") (pinfunction "2_2") (pintype "passive"))
      (node (ref "C3") (pin "2") (pinfunction "2_2") (pintype "passive"))
      (node (ref "C4") (pin "2") (pinfunction "2_2") (pintype "passive"))
      (node (ref "C6") (pin "2") (pinfunction "2_2") (pintype "passive"))
      (node (ref "C7") (pin "2") (pinfunction "2_2") (pintype "passive"))
      (node (ref "C8") (pin "2") (pinfunction "2_2") (pintype "passive"))
      (node (ref "J3") (pin "1") (pinfunction "A1_1") (pintype "passive"))
      (node (ref "J3") (pin "2") (pinfunction "A2_2") (pintype "passive"))
      (node (ref "J3") (pin "3") (pinfunction "A3_3") (pintype "passive"))
      (node (ref "J3") (pin "4") (pinfunction "A4_4") (pintype "passive"))
      (node (ref "J3") (pin "5") (pinfunction "A5_5") (pintype "passive"))
      (node (ref "J4") (pin "1") (pinfunction "A1_1") (pintype "passive"))
      (node (ref "J4") (pin "2") (pinfunction "A2_2") (pintype "passive"))
      (node (ref "J4") (pin "3") (pinfunction "A3_3") (pintype "passive"))
      (node (ref "J4") (pin "4") (pinfunction "A4_4") (pintype "passive"))
      (node (ref "J4") (pin "5") (pinfunction "A5_5") (pintype "passive"))
      (node (ref "JP1") (pin "4") (pinfunction "ID_4") (pintype "passive"))
      (node (ref "K1") (pin "3") (pinfunction "3_3") (pintype "passive"))
      (node (ref "K2") (pin "1") (pinfunction "1_1") (pintype "passive"))
      (node (ref "P4") (pin "5") (pinfunction "A5_5") (pintype "passive"))
      (node (ref "R11") (pin "2") (pinfunction "2_2") (pintype "passive"))
      (node (ref "R12") (pin "2") (pinfunction "2_2") (pintype "passive"))
      (node (ref "R13") (pin "2") (pinfunction "2_2") (pintype "passive"))
      (node (ref "R14") (pin "2") (pinfunction "2_2") (pintype "passive"))
      (node (ref "R15") (pin "2") (pinfunction "2_2") (pintype "passive"))
      (node (ref "R1_1") (pin "2") (pinfunction "2_2") (pintype "passive"))
      (node (ref "R21_1") (pin "2") (pinfunction "2_2") (pintype "passive"))
      (node (ref "R21_2") (pin "2") (pinfunction "2_2") (pintype "passive"))
      (node (ref "R2_1") (pin "2") (pinfunction "2_2") (pintype "passive"))
      (node (ref "SW1") (pin "2") (pintype "passive"))
      (node (ref "SW1") (pin "4") (pintype "passive"))
      (node (ref "U1") (pin "1") (pinfunction "ADJ/GND_1") (pintype "power_in"))
      (node (ref "U2") (pin "41") (pinfunction "VSS_41") (pintype "power_in"))
      (node (ref "U2") (pin "5") (pinfunction "VSS_5") (pintype "power_in"))
      (node (ref "U3") (pin "1") (pinfunction "GND_1") (pintype "power_in"))
    )
    (net (code "50") (name "unconnected-(JP1A-GND-Pad5)") (class "Default")
      (node (ref "JP1") (pin "5") (pinfunction "GND_5") (pintype "passive+no_connect"))
    )
    (net (code "51") (name "unconnected-(JP1B-SHIELD-Pad6)") (class "Default")
      (node (ref "JP1") (pin "6") (pinfunction "SHIELD_6") (pintype "passive+no_connect"))
    )
    (net (code "52") (name "unconnected-(JP1B-SHIELD-Pad7)") (class "Default")
      (node (ref "JP1") (pin "7") (pinfunction "SHIELD_7") (pintype "passive+no_connect"))
    )
    (net (code "53") (name "unconnected-(JP1B-SHIELD-Pad8)") (class "Default")
      (node (ref "JP1") (pin "8") (pinfunction "SHIELD_8") (pintype "passive+no_connect"))
    )
    (net (code "54") (name "unconnected-(JP1B-SHIELD-Pad9)") (class "Default")
      (node (ref "JP1") (pin "9") (pinfunction "SHIELD_9") (pintype "passive+no_connect"))
    )
    (net (code "55") (name "unconnected-(U2A-PI00_21{slash}CT16B1_MAT0{slash}MOSI1-Pad17)") (class "Default")
      (node (ref "U2") (pin "17") (pinfunction "PI00_21/CT16B1_MAT0/MOSI1_17") (pintype "bidirectional+no_connect"))
    )
    (net (code "56") (name "unconnected-(U2A-PIO0_7{slash}~{CTS}-Pad23)") (class "Default")
      (node (ref "U2") (pin "23") (pinfunction "PIO0_7/~{CTS}_23") (pintype "bidirectional+no_connect"))
    )
    (net (code "57") (name "unconnected-(U2A-PIO0_16{slash}AD5{slash}CT32B1_MAT3{slash}WAKEUP-Pad40)") (class "Default")
      (node (ref "U2") (pin "40") (pinfunction "PIO0_16/AD5/CT32B1_MAT3/WAKEUP_40") (pintype "bidirectional+no_connect"))
    )
    (net (code "58") (name "unconnected-(U2A-PIO0_17{slash}~{RTS}{slash}CT32B0_CAP0{slash}SCLK-Pad45)") (class "Default")
      (node (ref "U2") (pin "45") (pinfunction "PIO0_17/~{RTS}/CT32B0_CAP0/SCLK_45") (pintype "bidirectional+no_connect"))
    )
    (net (code "59") (name "unconnected-(U2A-PIO0_23{slash}AD7-Pad42)") (class "Default")
      (node (ref "U2") (pin "42") (pinfunction "PIO0_23/AD7_42") (pintype "bidirectional+no_connect"))
    )
    (net (code "60") (name "unconnected-(U2A-PIO1_15{slash}~{DCD}{slash}CT16B0_MAT2{slash}SCK1-Pad43)") (class "Default")
      (node (ref "U2") (pin "43") (pinfunction "PIO1_15/~{DCD}/CT16B0_MAT2/SCK1_43") (pintype "bidirectional+no_connect"))
    )
    (net (code "61") (name "unconnected-(U2A-PIO1_16{slash}~{RI}{slash}CT16B0_CAP0-Pad48)") (class "Default")
      (node (ref "U2") (pin "48") (pinfunction "PIO1_16/~{RI}/CT16B0_CAP0_48") (pintype "bidirectional+no_connect"))
    )
    (net (code "62") (name "unconnected-(U2A-PIO1_24{slash}CT32B0_MAT0-Pad21)") (class "Default")
      (node (ref "U2") (pin "21") (pinfunction "PIO1_24/CT32B0_MAT0_21") (pintype "bidirectional+no_connect"))
    )
    (net (code "63") (name "unconnected-(U2A-PIO1_28{slash}CT32B0_CAP0{slash}SCLK-Pad24)") (class "Default")
      (node (ref "U2") (pin "24") (pinfunction "PIO1_28/CT32B0_CAP0/SCLK_24") (pintype "bidirectional+no_connect"))
    )
    (net (code "64") (name "unconnected-(U2A-PIO1_29{slash}SCK0{slash}CT32B0_CAP1-Pad31)") (class "Default")
      (node (ref "U2") (pin "31") (pinfunction "PIO1_29/SCK0/CT32B0_CAP1_31") (pintype "bidirectional+no_connect"))
    )
    (net (code "65") (name "unconnected-(U2A-PIO1_31-Pad25)") (class "Default")
      (node (ref "U2") (pin "25") (pinfunction "PIO1_31_25") (pintype "bidirectional+no_connect"))
    )
  )
)
